# EstlCam_board_v3.net
KiCad netlist of a schematic drawn in EAGLE
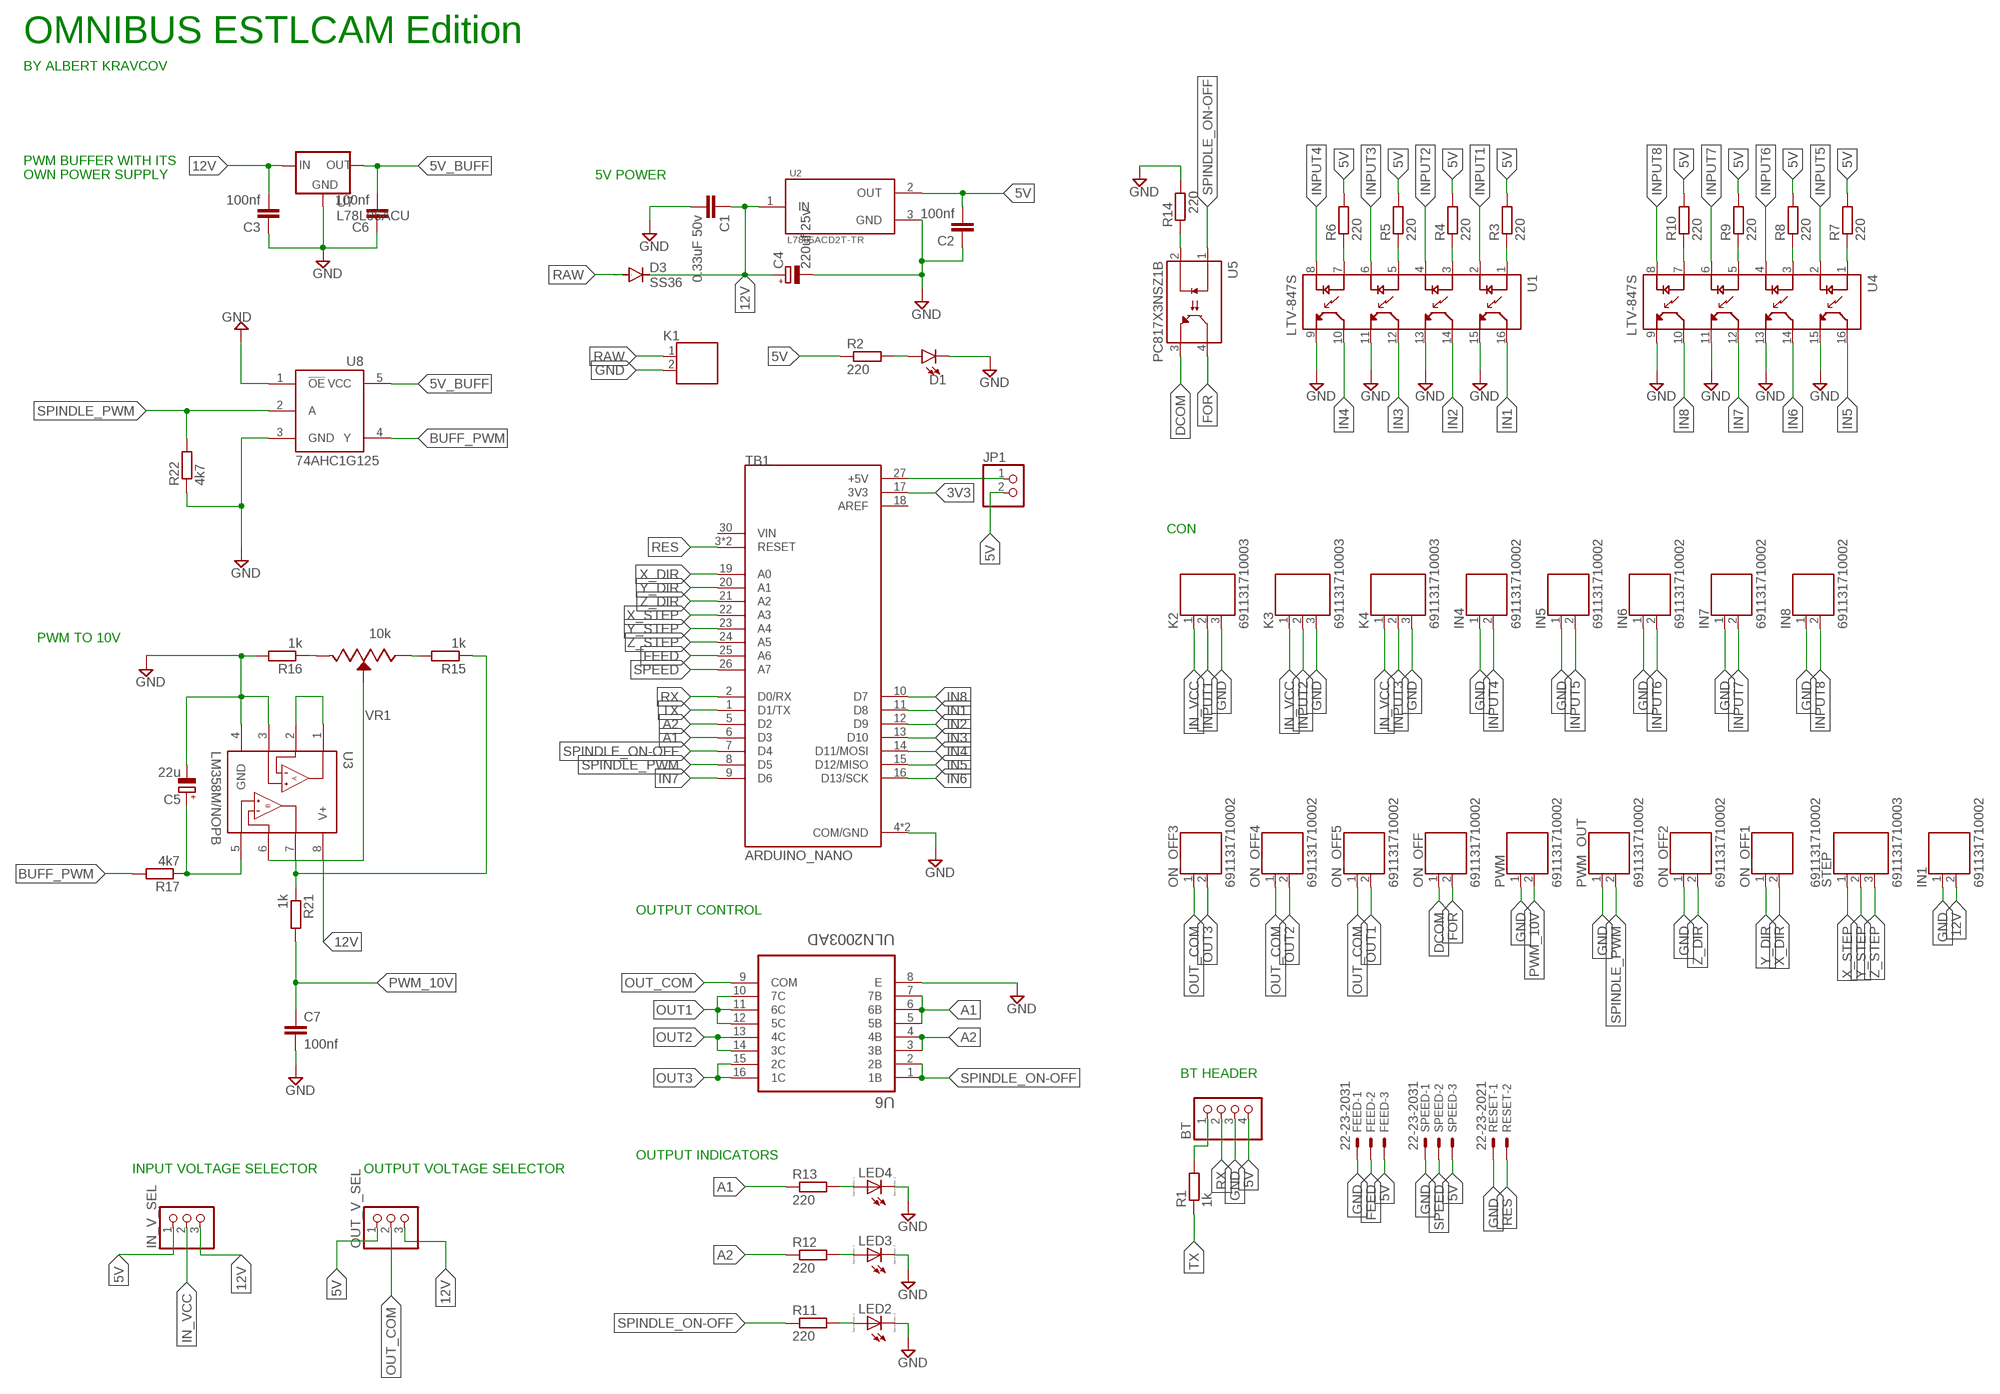
[diagram p0: schematic, sheet 1]

(export (version "E")
  (design (tool "Eeschema 10.0.6"))
  (components
    (comp (ref "BT")
      (value "PINHD-1X4")
      (footprint "eagle-import:1X04")
      (libsource (lib "eagle-import") (part "PINHD-1X4"))
    )
    (comp (ref "C1")
      (value "0.33uF 50v")
      (footprint "eagle-import:C1206")
      (libsource (lib "eagle-import") (part "C-EUC1206"))
    )
    (comp (ref "C2")
      (value "100nf")
      (footprint "eagle-import:C0805")
      (libsource (lib "eagle-import") (part "C-EUC0805"))
    )
    (comp (ref "C3")
      (value "100nf")
      (footprint "eagle-import:C0805")
      (libsource (lib "eagle-import") (part "C-EUC0805"))
    )
    (comp (ref "C4")
      (value "220uf 25v")
      (footprint "eagle-import:E5-6")
      (libsource (lib "eagle-import") (part "CPOL-EUE5-6"))
    )
    (comp (ref "C5")
      (value "22u")
      (footprint "eagle-import:E2-5")
      (libsource (lib "eagle-import") (part "CPOL-EUE2-5"))
    )
    (comp (ref "C6")
      (value "100nf")
      (footprint "eagle-import:C0805")
      (libsource (lib "eagle-import") (part "C-EUC0805"))
    )
    (comp (ref "C7")
      (value "100nf")
      (footprint "eagle-import:C0805")
      (libsource (lib "eagle-import") (part "C-EUC0805"))
    )
    (comp (ref "D1")
      (value "LED1206")
      (footprint "eagle-import:LED-1206")
      (libsource (lib "eagle-import") (part "LED1206"))
    )
    (comp (ref "D3")
      (value "SS36")
      (footprint "eagle-import:SMB")
      (libsource (lib "eagle-import") (part "ES2D"))
    )
    (comp (ref "FEED")
      (value "22-23-2031")
      (footprint "eagle-import:22-23-2031")
      (fields (field (name "MF") "MOLEX"))
      (libsource (lib "eagle-import") (part "22-23-2031"))
    )
    (comp (ref "IN1")
      (value "691131710002")
      (footprint "eagle-import:691131710002")
      (libsource (lib "eagle-import") (part "691131710002"))
    )
    (comp (ref "IN4")
      (value "691131710002")
      (footprint "eagle-import:691131710002")
      (libsource (lib "eagle-import") (part "691131710002"))
    )
    (comp (ref "IN5")
      (value "691131710002")
      (footprint "eagle-import:691131710002")
      (libsource (lib "eagle-import") (part "691131710002"))
    )
    (comp (ref "IN6")
      (value "691131710002")
      (footprint "eagle-import:691131710002")
      (libsource (lib "eagle-import") (part "691131710002"))
    )
    (comp (ref "IN7")
      (value "691131710002")
      (footprint "eagle-import:691131710002")
      (libsource (lib "eagle-import") (part "691131710002"))
    )
    (comp (ref "IN8")
      (value "691131710002")
      (footprint "eagle-import:691131710002")
      (libsource (lib "eagle-import") (part "691131710002"))
    )
    (comp (ref "IN_V_SEL")
      (value "PINHD-1X3")
      (footprint "eagle-import:1X03")
      (libsource (lib "eagle-import") (part "PINHD-1X3"))
    )
    (comp (ref "JP1")
      (value "PINHD-1X2")
      (footprint "eagle-import:1X02")
      (libsource (lib "eagle-import") (part "PINHD-1X2"))
    )
    (comp (ref "K1")
      (value "691131710002")
      (footprint "eagle-import:691131710002")
      (libsource (lib "eagle-import") (part "691131710002"))
    )
    (comp (ref "K2")
      (value "691131710003")
      (footprint "eagle-import:691131710003")
      (libsource (lib "eagle-import") (part "691131710003"))
    )
    (comp (ref "K3")
      (value "691131710003")
      (footprint "eagle-import:691131710003")
      (libsource (lib "eagle-import") (part "691131710003"))
    )
    (comp (ref "K4")
      (value "691131710003")
      (footprint "eagle-import:691131710003")
      (libsource (lib "eagle-import") (part "691131710003"))
    )
    (comp (ref "LED2")
      (value "LED_ESML0603")
      (footprint "eagle-import:LED_SML0603")
      (libsource (lib "eagle-import") (part "LED_ESML0603"))
    )
    (comp (ref "LED3")
      (value "LED_ESML0603")
      (footprint "eagle-import:LED_SML0603")
      (libsource (lib "eagle-import") (part "LED_ESML0603"))
    )
    (comp (ref "LED4")
      (value "LED_ESML0603")
      (footprint "eagle-import:LED_SML0603")
      (libsource (lib "eagle-import") (part "LED_ESML0603"))
    )
    (comp (ref "ON_OFF")
      (value "691131710002")
      (footprint "eagle-import:691131710002")
      (libsource (lib "eagle-import") (part "691131710002"))
    )
    (comp (ref "ON_OFF1")
      (value "691131710002")
      (footprint "eagle-import:691131710002")
      (libsource (lib "eagle-import") (part "691131710002"))
    )
    (comp (ref "ON_OFF2")
      (value "691131710002")
      (footprint "eagle-import:691131710002")
      (libsource (lib "eagle-import") (part "691131710002"))
    )
    (comp (ref "ON_OFF3")
      (value "691131710002")
      (footprint "eagle-import:691131710002")
      (libsource (lib "eagle-import") (part "691131710002"))
    )
    (comp (ref "ON_OFF4")
      (value "691131710002")
      (footprint "eagle-import:691131710002")
      (libsource (lib "eagle-import") (part "691131710002"))
    )
    (comp (ref "ON_OFF5")
      (value "691131710002")
      (footprint "eagle-import:691131710002")
      (libsource (lib "eagle-import") (part "691131710002"))
    )
    (comp (ref "OUT_V_SEL")
      (value "PINHD-1X3")
      (footprint "eagle-import:1X03")
      (libsource (lib "eagle-import") (part "PINHD-1X3"))
    )
    (comp (ref "PWM")
      (value "691131710002")
      (footprint "eagle-import:691131710002")
      (libsource (lib "eagle-import") (part "691131710002"))
    )
    (comp (ref "PWM_OUT")
      (value "691131710002")
      (footprint "eagle-import:691131710002")
      (libsource (lib "eagle-import") (part "691131710002"))
    )
    (comp (ref "R1")
      (value "1k")
      (footprint "eagle-import:R0805")
      (libsource (lib "eagle-import") (part "R-EU_R0805"))
    )
    (comp (ref "R2")
      (value "220")
      (footprint "eagle-import:R0805")
      (libsource (lib "eagle-import") (part "R-EU_R0805"))
    )
    (comp (ref "R3")
      (value "220")
      (footprint "eagle-import:R0805")
      (libsource (lib "eagle-import") (part "R-EU_R0805"))
    )
    (comp (ref "R4")
      (value "220")
      (footprint "eagle-import:R0805")
      (libsource (lib "eagle-import") (part "R-EU_R0805"))
    )
    (comp (ref "R5")
      (value "220")
      (footprint "eagle-import:R0805")
      (libsource (lib "eagle-import") (part "R-EU_R0805"))
    )
    (comp (ref "R6")
      (value "220")
      (footprint "eagle-import:R0805")
      (libsource (lib "eagle-import") (part "R-EU_R0805"))
    )
    (comp (ref "R7")
      (value "220")
      (footprint "eagle-import:R0805")
      (libsource (lib "eagle-import") (part "R-EU_R0805"))
    )
    (comp (ref "R8")
      (value "220")
      (footprint "eagle-import:R0805")
      (libsource (lib "eagle-import") (part "R-EU_R0805"))
    )
    (comp (ref "R9")
      (value "220")
      (footprint "eagle-import:R0805")
      (libsource (lib "eagle-import") (part "R-EU_R0805"))
    )
    (comp (ref "R10")
      (value "220")
      (footprint "eagle-import:R0805")
      (libsource (lib "eagle-import") (part "R-EU_R0805"))
    )
    (comp (ref "R11")
      (value "220")
      (footprint "eagle-import:R0603")
      (libsource (lib "eagle-import") (part "R-EU_R0603"))
    )
    (comp (ref "R12")
      (value "220")
      (footprint "eagle-import:R0603")
      (libsource (lib "eagle-import") (part "R-EU_R0603"))
    )
    (comp (ref "R13")
      (value "220")
      (footprint "eagle-import:R0603")
      (libsource (lib "eagle-import") (part "R-EU_R0603"))
    )
    (comp (ref "R14")
      (value "220")
      (footprint "eagle-import:R0805")
      (libsource (lib "eagle-import") (part "R-EU_R0805"))
    )
    (comp (ref "R15")
      (value "1k")
      (footprint "eagle-import:R0805")
      (libsource (lib "eagle-import") (part "R-EU_R0805"))
    )
    (comp (ref "R16")
      (value "1k")
      (footprint "eagle-import:R0805")
      (libsource (lib "eagle-import") (part "R-EU_R0805"))
    )
    (comp (ref "R17")
      (value "4k7")
      (footprint "eagle-import:R0603")
      (libsource (lib "eagle-import") (part "R-EU_R0603"))
    )
    (comp (ref "R21")
      (value "1k")
      (footprint "eagle-import:R0805")
      (libsource (lib "eagle-import") (part "R-EU_R0805"))
    )
    (comp (ref "R22")
      (value "4k7")
      (footprint "eagle-import:R0805")
      (libsource (lib "eagle-import") (part "R-EU_R0805"))
    )
    (comp (ref "RESET")
      (value "22-23-2021")
      (footprint "eagle-import:22-23-2021")
      (fields (field (name "MF") "MOLEX"))
      (libsource (lib "eagle-import") (part "22-23-2021"))
    )
    (comp (ref "SPEED")
      (value "22-23-2031")
      (footprint "eagle-import:22-23-2031")
      (fields (field (name "MF") "MOLEX"))
      (libsource (lib "eagle-import") (part "22-23-2031"))
    )
    (comp (ref "STEP")
      (value "691131710003")
      (footprint "eagle-import:691131710003")
      (libsource (lib "eagle-import") (part "691131710003"))
    )
    (comp (ref "TB1")
      (value "ARDUINO_NANO")
      (footprint "eagle-import:SHIELD_ARDUINO_NANO")
      (fields (field (name "MF") "Arduino") (field (name "MP") "ARDUINO NANO"))
      (libsource (lib "eagle-import") (part "ARDUINO_NANO"))
    )
    (comp (ref "U1")
      (value "LTV-847S")
      (footprint "eagle-import:SOIC254P1016X460-16N")
      (fields (field (name "MF") "Lite-On Inc."))
      (libsource (lib "eagle-import") (part "LTV-847S"))
    )
    (comp (ref "U2")
      (value "L7805ACD2T-TR")
      (footprint "eagle-import:TO254P1515X470-3N")
      (fields (field (name "MF") "STMicroelectronics"))
      (libsource (lib "eagle-import") (part "L7805ACD2T-TR"))
    )
    (comp (ref "U3")
      (value "LM358M/NOPB")
      (footprint "eagle-import:SOIC127P599X175-8N")
      (fields (field (name "MF") "Texas Instruments") (field (name "MP") "LM358M"))
      (libsource (lib "eagle-import") (part "LM358M/NOPB"))
    )
    (comp (ref "U4")
      (value "LTV-847S")
      (footprint "eagle-import:SOIC254P1016X460-16N")
      (fields (field (name "MF") "Lite-On Inc."))
      (libsource (lib "eagle-import") (part "LTV-847S"))
    )
    (comp (ref "U5")
      (value "PC817X3NSZ1B")
      (footprint "eagle-import:DIP762W50P254L495H455Q4")
      (fields (field (name "MF") "Sharp Microelectronics"))
      (libsource (lib "eagle-import") (part "PC817X3NSZ1B"))
    )
    (comp (ref "U6")
      (value "ULN2003AD")
      (footprint "eagle-import:SOIC127P600X175-16N")
      (fields (field (name "MF") "Texas Instruments"))
      (libsource (lib "eagle-import") (part "ULN2003AD"))
    )
    (comp (ref "U7")
      (value "L78L05ACU")
      (footprint "eagle-import:SOT89")
      (fields (field (name "MF") "STMicroelectronics"))
      (libsource (lib "eagle-import") (part "L78L05ACU"))
    )
    (comp (ref "U8")
      (value "74AHC1G125")
      (footprint "eagle-import:SOT23-5L")
      (fields (field (name "MF") "Texas Instruments"))
      (libsource (lib "eagle-import") (part "74AHC1G125"))
    )
    (comp (ref "VR1")
      (value "10k")
      (footprint "eagle-import:TRIM_3296W-1-502")
      (fields (field (name "MF") "Bourns") (field (name "MP") "3296W-1-502"))
      (libsource (lib "eagle-import") (part "3296W-1-502"))
    )
  )
  (nets
    (net (code "1") (name "/AREF") (class "Default")
      (node (ref "TB1") (pin "18") (pinfunction "AREF_18") (pintype "power_in"))
    )
    (net (code "2") (name "3V3") (class "Default")
      (node (ref "TB1") (pin "17") (pinfunction "3V3_17") (pintype "power_in"))
    )
    (net (code "3") (name "5V") (class "Default")
      (node (ref "BT") (pin "4") (pinfunction "4_4") (pintype "passive"))
      (node (ref "C2") (pin "2") (pinfunction "2_2") (pintype "passive"))
      (node (ref "FEED") (pin "3") (pinfunction "S_3") (pintype "passive"))
      (node (ref "IN_V_SEL") (pin "1") (pinfunction "1_1") (pintype "passive"))
      (node (ref "JP1") (pin "2") (pinfunction "2_2") (pintype "passive"))
      (node (ref "OUT_V_SEL") (pin "1") (pinfunction "1_1") (pintype "passive"))
      (node (ref "R10") (pin "2") (pinfunction "2_2") (pintype "passive"))
      (node (ref "R2") (pin "1") (pinfunction "1_1") (pintype "passive"))
      (node (ref "R3") (pin "2") (pinfunction "2_2") (pintype "passive"))
      (node (ref "R4") (pin "2") (pinfunction "2_2") (pintype "passive"))
      (node (ref "R5") (pin "2") (pinfunction "2_2") (pintype "passive"))
      (node (ref "R6") (pin "2") (pinfunction "2_2") (pintype "passive"))
      (node (ref "R7") (pin "2") (pinfunction "2_2") (pintype "passive"))
      (node (ref "R8") (pin "2") (pinfunction "2_2") (pintype "passive"))
      (node (ref "R9") (pin "2") (pinfunction "2_2") (pintype "passive"))
      (node (ref "SPEED") (pin "3") (pinfunction "S_3") (pintype "passive"))
      (node (ref "U2") (pin "2") (pinfunction "OUT_2") (pintype "output"))
    )
    (net (code "4") (name "5V_BUFF") (class "Default")
      (node (ref "C6") (pin "2") (pinfunction "2_2") (pintype "passive"))
      (node (ref "U7") (pin "1") (pinfunction "OUT_1") (pintype "output"))
      (node (ref "U8") (pin "5") (pinfunction "VCC_5") (pintype "power_in"))
    )
    (net (code "5") (name "12V") (class "Default")
      (node (ref "C1") (pin "1") (pinfunction "1_1") (pintype "passive"))
      (node (ref "C3") (pin "2") (pinfunction "2_2") (pintype "passive"))
      (node (ref "C4") (pin "+") (pinfunction "+_+") (pintype "passive"))
      (node (ref "D3") (pin "C") (pinfunction "C_C") (pintype "passive"))
      (node (ref "IN1") (pin "2") (pinfunction "2_2") (pintype "passive"))
      (node (ref "IN_V_SEL") (pin "3") (pinfunction "3_3") (pintype "passive"))
      (node (ref "OUT_V_SEL") (pin "3") (pinfunction "3_3") (pintype "passive"))
      (node (ref "U2") (pin "1") (pinfunction "IN_1") (pintype "input"))
      (node (ref "U3") (pin "8") (pinfunction "V+_8") (pintype "power_in"))
      (node (ref "U7") (pin "3") (pinfunction "IN_3") (pintype "input"))
    )
    (net (code "6") (name "A1") (class "Default")
      (node (ref "R13") (pin "1") (pinfunction "1_1") (pintype "passive"))
      (node (ref "TB1") (pin "6") (pinfunction "D3_6") (pintype "bidirectional"))
      (node (ref "U6") (pin "5") (pinfunction "5B_5") (pintype "input"))
      (node (ref "U6") (pin "6") (pinfunction "6B_6") (pintype "input"))
      (node (ref "U6") (pin "7") (pinfunction "7B_7") (pintype "input"))
    )
    (net (code "7") (name "A2") (class "Default")
      (node (ref "R12") (pin "1") (pinfunction "1_1") (pintype "passive"))
      (node (ref "TB1") (pin "5") (pinfunction "D2_5") (pintype "bidirectional"))
      (node (ref "U6") (pin "3") (pinfunction "3B_3") (pintype "input"))
      (node (ref "U6") (pin "4") (pinfunction "4B_4") (pintype "input"))
    )
    (net (code "8") (name "BUFF_PWM") (class "Default")
      (node (ref "R17") (pin "2") (pinfunction "2_2") (pintype "passive"))
      (node (ref "U8") (pin "4") (pinfunction "Y_4") (pintype "output"))
    )
    (net (code "9") (name "DCOM") (class "Default")
      (node (ref "ON_OFF") (pin "1") (pinfunction "1_1") (pintype "passive"))
      (node (ref "U5") (pin "3") (pinfunction "EMITTER_3") (pintype "passive"))
    )
    (net (code "10") (name "FEED") (class "Default")
      (node (ref "FEED") (pin "2") (pinfunction "S_2") (pintype "passive"))
      (node (ref "TB1") (pin "25") (pinfunction "A6_25") (pintype "input"))
    )
    (net (code "11") (name "FOR") (class "Default")
      (node (ref "ON_OFF") (pin "2") (pinfunction "2_2") (pintype "passive"))
      (node (ref "U5") (pin "4") (pinfunction "COLLECTOR_4") (pintype "passive"))
    )
    (net (code "12") (name "GND") (class "Default")
      (node (ref "BT") (pin "3") (pinfunction "3_3") (pintype "passive"))
      (node (ref "C1") (pin "2") (pinfunction "2_2") (pintype "passive"))
      (node (ref "C2") (pin "1") (pinfunction "1_1") (pintype "passive"))
      (node (ref "C3") (pin "1") (pinfunction "1_1") (pintype "passive"))
      (node (ref "C4") (pin "-") (pinfunction "-_-") (pintype "passive"))
      (node (ref "C5") (pin "-") (pinfunction "-_-") (pintype "passive"))
      (node (ref "C6") (pin "1") (pinfunction "1_1") (pintype "passive"))
      (node (ref "C7") (pin "2") (pinfunction "2_2") (pintype "passive"))
      (node (ref "D1") (pin "C") (pinfunction "C_C") (pintype "passive"))
      (node (ref "FEED") (pin "1") (pinfunction "S_1") (pintype "passive"))
      (node (ref "IN1") (pin "1") (pinfunction "1_1") (pintype "passive"))
      (node (ref "IN4") (pin "1") (pinfunction "1_1") (pintype "passive"))
      (node (ref "IN5") (pin "1") (pinfunction "1_1") (pintype "passive"))
      (node (ref "IN6") (pin "1") (pinfunction "1_1") (pintype "passive"))
      (node (ref "IN7") (pin "1") (pinfunction "1_1") (pintype "passive"))
      (node (ref "IN8") (pin "1") (pinfunction "1_1") (pintype "passive"))
      (node (ref "K1") (pin "2") (pinfunction "2_2") (pintype "passive"))
      (node (ref "K2") (pin "3") (pinfunction "3_3") (pintype "passive"))
      (node (ref "K3") (pin "3") (pinfunction "3_3") (pintype "passive"))
      (node (ref "K4") (pin "3") (pinfunction "3_3") (pintype "passive"))
      (node (ref "LED2") (pin "C") (pinfunction "C_C") (pintype "passive"))
      (node (ref "LED3") (pin "C") (pinfunction "C_C") (pintype "passive"))
      (node (ref "LED4") (pin "C") (pinfunction "C_C") (pintype "passive"))
      (node (ref "ON_OFF2") (pin "1") (pinfunction "1_1") (pintype "passive"))
      (node (ref "PWM") (pin "1") (pinfunction "1_1") (pintype "passive"))
      (node (ref "PWM_OUT") (pin "1") (pinfunction "1_1") (pintype "passive"))
      (node (ref "R14") (pin "2") (pinfunction "2_2") (pintype "passive"))
      (node (ref "R16") (pin "2") (pinfunction "2_2") (pintype "passive"))
      (node (ref "R22") (pin "1") (pinfunction "1_1") (pintype "passive"))
      (node (ref "RESET") (pin "1") (pinfunction "S_1") (pintype "passive"))
      (node (ref "SPEED") (pin "1") (pinfunction "S_1") (pintype "passive"))
      (node (ref "TB1") (pin "29") (pinfunction "COM/GND_29") (pintype "power_in"))
      (node (ref "TB1") (pin "4") (pinfunction "COM/GND_4") (pintype "power_in"))
      (node (ref "U1") (pin "11") (pinfunction "ET2_11") (pintype "passive"))
      (node (ref "U1") (pin "13") (pinfunction "ET1_13") (pintype "passive"))
      (node (ref "U1") (pin "15") (pinfunction "ET_15") (pintype "passive"))
      (node (ref "U1") (pin "9") (pinfunction "ET3_9") (pintype "passive"))
      (node (ref "U2") (pin "3") (pinfunction "GND_3") (pintype "power_in"))
      (node (ref "U3") (pin "3") (pinfunction "+INA_3") (pintype "input"))
      (node (ref "U3") (pin "4") (pinfunction "GND_4") (pintype "power_in"))
      (node (ref "U4") (pin "11") (pinfunction "ET2_11") (pintype "passive"))
      (node (ref "U4") (pin "13") (pinfunction "ET1_13") (pintype "passive"))
      (node (ref "U4") (pin "15") (pinfunction "ET_15") (pintype "passive"))
      (node (ref "U4") (pin "9") (pinfunction "ET3_9") (pintype "passive"))
      (node (ref "U6") (pin "8") (pinfunction "E_8") (pintype "input"))
      (node (ref "U7") (pin "2") (pinfunction "GND_2") (pintype "input"))
      (node (ref "U8") (pin "1") (pinfunction "~{OE}_1") (pintype "input"))
      (node (ref "U8") (pin "3") (pinfunction "GND_3") (pintype "power_in"))
    )
    (net (code "13") (name "IN1") (class "Default")
      (node (ref "TB1") (pin "11") (pinfunction "D8_11") (pintype "bidirectional"))
      (node (ref "U1") (pin "16") (pinfunction "CT_16") (pintype "passive"))
    )
    (net (code "14") (name "IN2") (class "Default")
      (node (ref "TB1") (pin "12") (pinfunction "D9_12") (pintype "bidirectional"))
      (node (ref "U1") (pin "14") (pinfunction "CT1_14") (pintype "passive"))
    )
    (net (code "15") (name "IN3") (class "Default")
      (node (ref "TB1") (pin "13") (pinfunction "D10_13") (pintype "bidirectional"))
      (node (ref "U1") (pin "12") (pinfunction "CT2_12") (pintype "passive"))
    )
    (net (code "16") (name "IN4") (class "Default")
      (node (ref "TB1") (pin "14") (pinfunction "D11/MOSI_14") (pintype "bidirectional"))
      (node (ref "U1") (pin "10") (pinfunction "CT3_10") (pintype "passive"))
    )
    (net (code "17") (name "IN5") (class "Default")
      (node (ref "TB1") (pin "15") (pinfunction "D12/MISO_15") (pintype "bidirectional"))
      (node (ref "U4") (pin "16") (pinfunction "CT_16") (pintype "passive"))
    )
    (net (code "18") (name "IN6") (class "Default")
      (node (ref "TB1") (pin "16") (pinfunction "D13/SCK_16") (pintype "bidirectional"))
      (node (ref "U4") (pin "14") (pinfunction "CT1_14") (pintype "passive"))
    )
    (net (code "19") (name "IN7") (class "Default")
      (node (ref "TB1") (pin "9") (pinfunction "D6_9") (pintype "bidirectional"))
      (node (ref "U4") (pin "12") (pinfunction "CT2_12") (pintype "passive"))
    )
    (net (code "20") (name "IN8") (class "Default")
      (node (ref "TB1") (pin "10") (pinfunction "D7_10") (pintype "bidirectional"))
      (node (ref "U4") (pin "10") (pinfunction "CT3_10") (pintype "passive"))
    )
    (net (code "21") (name "INPUT1") (class "Default")
      (node (ref "K2") (pin "2") (pinfunction "2_2") (pintype "passive"))
      (node (ref "U1") (pin "2") (pinfunction "C_2") (pintype "passive"))
    )
    (net (code "22") (name "INPUT2") (class "Default")
      (node (ref "K3") (pin "2") (pinfunction "2_2") (pintype "passive"))
      (node (ref "U1") (pin "4") (pinfunction "C1_4") (pintype "passive"))
    )
    (net (code "23") (name "INPUT3") (class "Default")
      (node (ref "K4") (pin "2") (pinfunction "2_2") (pintype "passive"))
      (node (ref "U1") (pin "6") (pinfunction "C2_6") (pintype "passive"))
    )
    (net (code "24") (name "INPUT4") (class "Default")
      (node (ref "IN4") (pin "2") (pinfunction "2_2") (pintype "passive"))
      (node (ref "U1") (pin "8") (pinfunction "C3_8") (pintype "passive"))
    )
    (net (code "25") (name "INPUT5") (class "Default")
      (node (ref "IN5") (pin "2") (pinfunction "2_2") (pintype "passive"))
      (node (ref "U4") (pin "2") (pinfunction "C_2") (pintype "passive"))
    )
    (net (code "26") (name "INPUT6") (class "Default")
      (node (ref "IN6") (pin "2") (pinfunction "2_2") (pintype "passive"))
      (node (ref "U4") (pin "4") (pinfunction "C1_4") (pintype "passive"))
    )
    (net (code "27") (name "INPUT7") (class "Default")
      (node (ref "IN7") (pin "2") (pinfunction "2_2") (pintype "passive"))
      (node (ref "U4") (pin "6") (pinfunction "C2_6") (pintype "passive"))
    )
    (net (code "28") (name "INPUT8") (class "Default")
      (node (ref "IN8") (pin "2") (pinfunction "2_2") (pintype "passive"))
      (node (ref "U4") (pin "8") (pinfunction "C3_8") (pintype "passive"))
    )
    (net (code "29") (name "IN_VCC") (class "Default")
      (node (ref "IN_V_SEL") (pin "2") (pinfunction "2_2") (pintype "passive"))
      (node (ref "K2") (pin "1") (pinfunction "1_1") (pintype "passive"))
      (node (ref "K3") (pin "1") (pinfunction "1_1") (pintype "passive"))
      (node (ref "K4") (pin "1") (pinfunction "1_1") (pintype "passive"))
    )
    (net (code "30") (name "Net-(BT-Pad1)") (class "Default")
      (node (ref "BT") (pin "1") (pinfunction "1_1") (pintype "passive"))
      (node (ref "R1") (pin "2") (pinfunction "2_2") (pintype "passive"))
    )
    (net (code "31") (name "Net-(D1-PadA)") (class "Default")
      (node (ref "D1") (pin "A") (pinfunction "A_A") (pintype "passive"))
      (node (ref "R2") (pin "2") (pinfunction "2_2") (pintype "passive"))
    )
    (net (code "32") (name "Net-(LED2-PadA)") (class "Default")
      (node (ref "LED2") (pin "A") (pinfunction "A_A") (pintype "passive"))
      (node (ref "R11") (pin "2") (pinfunction "2_2") (pintype "passive"))
    )
    (net (code "33") (name "Net-(LED3-PadA)") (class "Default")
      (node (ref "LED3") (pin "A") (pinfunction "A_A") (pintype "passive"))
      (node (ref "R12") (pin "2") (pinfunction "2_2") (pintype "passive"))
    )
    (net (code "34") (name "Net-(LED4-PadA)") (class "Default")
      (node (ref "LED4") (pin "A") (pinfunction "A_A") (pintype "passive"))
      (node (ref "R13") (pin "2") (pinfunction "2_2") (pintype "passive"))
    )
    (net (code "35") (name "Net-(TB1-+5V)") (class "Default")
      (node (ref "JP1") (pin "1") (pinfunction "1_1") (pintype "passive"))
      (node (ref "TB1") (pin "27") (pinfunction "+5V_27") (pintype "power_in"))
    )
    (net (code "36") (name "Net-(U1-A)") (class "Default")
      (node (ref "R3") (pin "1") (pinfunction "1_1") (pintype "passive"))
      (node (ref "U1") (pin "1") (pinfunction "A_1") (pintype "passive"))
    )
    (net (code "37") (name "Net-(U1-A1)") (class "Default")
      (node (ref "R4") (pin "1") (pinfunction "1_1") (pintype "passive"))
      (node (ref "U1") (pin "3") (pinfunction "A1_3") (pintype "passive"))
    )
    (net (code "38") (name "Net-(U1-A2)") (class "Default")
      (node (ref "R5") (pin "1") (pinfunction "1_1") (pintype "passive"))
      (node (ref "U1") (pin "5") (pinfunction "A2_5") (pintype "passive"))
    )
    (net (code "39") (name "Net-(U1-A3)") (class "Default")
      (node (ref "R6") (pin "1") (pinfunction "1_1") (pintype "passive"))
      (node (ref "U1") (pin "7") (pinfunction "A3_7") (pintype "passive"))
    )
    (net (code "40") (name "Net-(U3-+INB)") (class "Default")
      (node (ref "C5") (pin "+") (pinfunction "+_+") (pintype "passive"))
      (node (ref "R17") (pin "1") (pinfunction "1_1") (pintype "passive"))
      (node (ref "U3") (pin "5") (pinfunction "+INB_5") (pintype "input"))
    )
    (net (code "41") (name "Net-(U3--INA)") (class "Default")
      (node (ref "U3") (pin "1") (pinfunction "OUTA_1") (pintype "output"))
      (node (ref "U3") (pin "2") (pinfunction "-INA_2") (pintype "input"))
    )
    (net (code "42") (name "Net-(U3--INB)") (class "Default")
      (node (ref "U3") (pin "6") (pinfunction "-INB_6") (pintype "input"))
      (node (ref "VR1") (pin "2") (pinfunction "WIPER_2") (pintype "passive"))
    )
    (net (code "43") (name "Net-(U3-OUTB)") (class "Default")
      (node (ref "R15") (pin "1") (pinfunction "1_1") (pintype "passive"))
      (node (ref "R21") (pin "1") (pinfunction "1_1") (pintype "passive"))
      (node (ref "U3") (pin "7") (pinfunction "OUTB_7") (pintype "output"))
    )
    (net (code "44") (name "Net-(U4-A)") (class "Default")
      (node (ref "R7") (pin "1") (pinfunction "1_1") (pintype "passive"))
      (node (ref "U4") (pin "1") (pinfunction "A_1") (pintype "passive"))
    )
    (net (code "45") (name "Net-(U4-A1)") (class "Default")
      (node (ref "R8") (pin "1") (pinfunction "1_1") (pintype "passive"))
      (node (ref "U4") (pin "3") (pinfunction "A1_3") (pintype "passive"))
    )
    (net (code "46") (name "Net-(U4-A2)") (class "Default")
      (node (ref "R9") (pin "1") (pinfunction "1_1") (pintype "passive"))
      (node (ref "U4") (pin "5") (pinfunction "A2_5") (pintype "passive"))
    )
    (net (code "47") (name "Net-(U4-A3)") (class "Default")
      (node (ref "R10") (pin "1") (pinfunction "1_1") (pintype "passive"))
      (node (ref "U4") (pin "7") (pinfunction "A3_7") (pintype "passive"))
    )
    (net (code "48") (name "Net-(U5-CATHODE)") (class "Default")
      (node (ref "R14") (pin "1") (pinfunction "1_1") (pintype "passive"))
      (node (ref "U5") (pin "2") (pinfunction "CATHODE_2") (pintype "passive"))
    )
    (net (code "49") (name "Net-(VR1-CCW)") (class "Default")
      (node (ref "R15") (pin "2") (pinfunction "2_2") (pintype "passive"))
      (node (ref "VR1") (pin "1") (pinfunction "CCW_1") (pintype "passive"))
    )
    (net (code "50") (name "Net-(VR1-CW)") (class "Default")
      (node (ref "R16") (pin "1") (pinfunction "1_1") (pintype "passive"))
      (node (ref "VR1") (pin "3") (pinfunction "CW_3") (pintype "passive"))
    )
    (net (code "51") (name "OUT1") (class "Default")
      (node (ref "ON_OFF5") (pin "2") (pinfunction "2_2") (pintype "passive"))
      (node (ref "U6") (pin "10") (pinfunction "7C_10") (pintype "output"))
      (node (ref "U6") (pin "11") (pinfunction "6C_11") (pintype "output"))
      (node (ref "U6") (pin "12") (pinfunction "5C_12") (pintype "output"))
    )
    (net (code "52") (name "OUT2") (class "Default")
      (node (ref "ON_OFF4") (pin "2") (pinfunction "2_2") (pintype "passive"))
      (node (ref "U6") (pin "13") (pinfunction "4C_13") (pintype "output"))
      (node (ref "U6") (pin "14") (pinfunction "3C_14") (pintype "output"))
    )
    (net (code "53") (name "OUT3") (class "Default")
      (node (ref "ON_OFF3") (pin "2") (pinfunction "2_2") (pintype "passive"))
      (node (ref "U6") (pin "15") (pinfunction "2C_15") (pintype "output"))
      (node (ref "U6") (pin "16") (pinfunction "1C_16") (pintype "output"))
    )
    (net (code "54") (name "OUT_COM") (class "Default")
      (node (ref "ON_OFF3") (pin "1") (pinfunction "1_1") (pintype "passive"))
      (node (ref "ON_OFF4") (pin "1") (pinfunction "1_1") (pintype "passive"))
      (node (ref "ON_OFF5") (pin "1") (pinfunction "1_1") (pintype "passive"))
      (node (ref "OUT_V_SEL") (pin "2") (pinfunction "2_2") (pintype "passive"))
      (node (ref "U6") (pin "9") (pinfunction "COM_9") (pintype "output"))
    )
    (net (code "55") (name "PWM_10V") (class "Default")
      (node (ref "C7") (pin "1") (pinfunction "1_1") (pintype "passive"))
      (node (ref "PWM") (pin "2") (pinfunction "2_2") (pintype "passive"))
      (node (ref "R21") (pin "2") (pinfunction "2_2") (pintype "passive"))
    )
    (net (code "56") (name "RAW") (class "Default")
      (node (ref "D3") (pin "A") (pinfunction "A_A") (pintype "passive"))
      (node (ref "K1") (pin "1") (pinfunction "1_1") (pintype "passive"))
    )
    (net (code "57") (name "RES") (class "Default")
      (node (ref "RESET") (pin "2") (pinfunction "S_2") (pintype "passive"))
      (node (ref "TB1") (pin "28") (pinfunction "RESET_28") (pintype "input"))
      (node (ref "TB1") (pin "3") (pinfunction "RESET_3") (pintype "input"))
    )
    (net (code "58") (name "RX") (class "Default")
      (node (ref "BT") (pin "2") (pinfunction "2_2") (pintype "passive"))
      (node (ref "TB1") (pin "2") (pinfunction "D0/RX_2") (pintype "bidirectional"))
    )
    (net (code "59") (name "SPEED") (class "Default")
      (node (ref "SPEED") (pin "2") (pinfunction "S_2") (pintype "passive"))
      (node (ref "TB1") (pin "26") (pinfunction "A7_26") (pintype "input"))
    )
    (net (code "60") (name "SPINDLE_ON-OFF") (class "Default")
      (node (ref "R11") (pin "1") (pinfunction "1_1") (pintype "passive"))
      (node (ref "TB1") (pin "7") (pinfunction "D4_7") (pintype "bidirectional"))
      (node (ref "U5") (pin "1") (pinfunction "ANODE_1") (pintype "passive"))
      (node (ref "U6") (pin "1") (pinfunction "1B_1") (pintype "input"))
      (node (ref "U6") (pin "2") (pinfunction "2B_2") (pintype "input"))
    )
    (net (code "61") (name "SPINDLE_PWM") (class "Default")
      (node (ref "PWM_OUT") (pin "2") (pinfunction "2_2") (pintype "passive"))
      (node (ref "R22") (pin "2") (pinfunction "2_2") (pintype "passive"))
      (node (ref "TB1") (pin "8") (pinfunction "D5_8") (pintype "bidirectional"))
      (node (ref "U8") (pin "2") (pinfunction "A_2") (pintype "input"))
    )
    (net (code "62") (name "TX") (class "Default")
      (node (ref "R1") (pin "1") (pinfunction "1_1") (pintype "passive"))
      (node (ref "TB1") (pin "1") (pinfunction "D1/TX_1") (pintype "bidirectional"))
    )
    (net (code "63") (name "X_DIR") (class "Default")
      (node (ref "ON_OFF1") (pin "2") (pinfunction "2_2") (pintype "passive"))
      (node (ref "TB1") (pin "19") (pinfunction "A0_19") (pintype "input"))
    )
    (net (code "64") (name "X_STEP") (class "Default")
      (node (ref "STEP") (pin "1") (pinfunction "1_1") (pintype "passive"))
      (node (ref "TB1") (pin "22") (pinfunction "A3_22") (pintype "input"))
    )
    (net (code "65") (name "Y_DIR") (class "Default")
      (node (ref "ON_OFF1") (pin "1") (pinfunction "1_1") (pintype "passive"))
      (node (ref "TB1") (pin "20") (pinfunction "A1_20") (pintype "input"))
    )
    (net (code "66") (name "Y_STEP") (class "Default")
      (node (ref "STEP") (pin "2") (pinfunction "2_2") (pintype "passive"))
      (node (ref "TB1") (pin "23") (pinfunction "A4_23") (pintype "input"))
    )
    (net (code "67") (name "Z_DIR") (class "Default")
      (node (ref "ON_OFF2") (pin "2") (pinfunction "2_2") (pintype "passive"))
      (node (ref "TB1") (pin "21") (pinfunction "A2_21") (pintype "input"))
    )
    (net (code "68") (name "Z_STEP") (class "Default")
      (node (ref "STEP") (pin "3") (pinfunction "3_3") (pintype "passive"))
      (node (ref "TB1") (pin "24") (pinfunction "A5_24") (pintype "input"))
    )
    (net (code "69") (name "unconnected-(TB1-VIN-Pad30)") (class "Default")
      (node (ref "TB1") (pin "30") (pinfunction "VIN_30") (pintype "input"))
    )
  )
)
